# MovingHeadV2.net
KiCad netlist of a schematic drawn in EAGLE
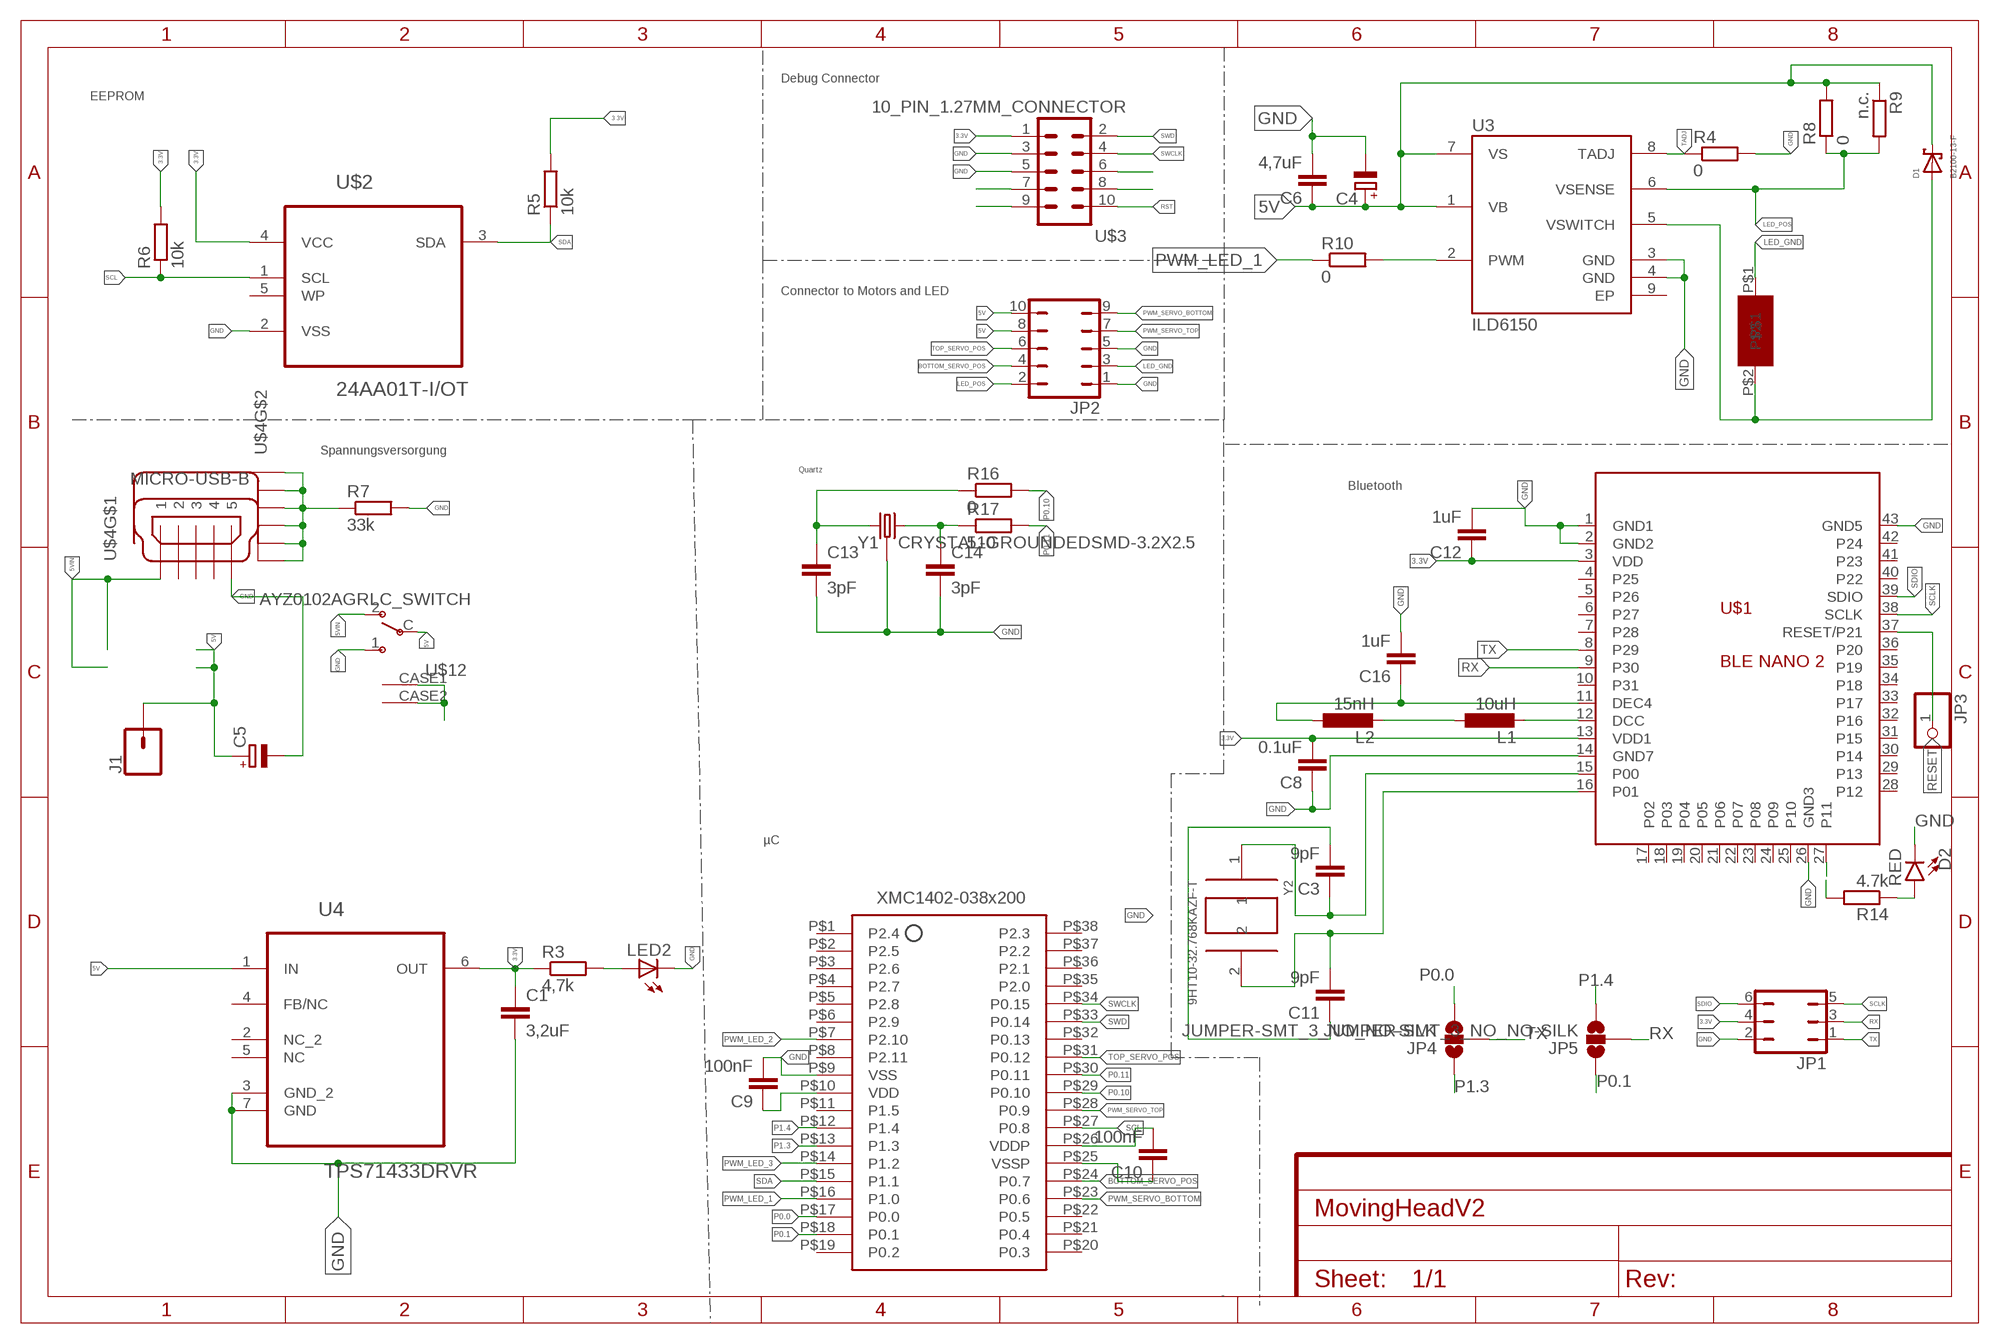
[diagram p0: schematic, sheet 1]

(export (version "E")
  (design (tool "Eeschema 10.0.6"))
  (components
    (comp (ref "C1")
      (value "3,2uF")
      (footprint "eagle-import:C0805")
      (libsource (lib "eagle-import") (part "rcl_334_C-EUC0805"))
    )
    (comp (ref "C3")
      (value "9pF")
      (footprint "eagle-import:C0805")
      (libsource (lib "eagle-import") (part "C-EUC0805"))
    )
    (comp (ref "C4")
      (value "CPOL-EUD")
      (footprint "eagle-import:PANASONIC_D")
      (libsource (lib "eagle-import") (part "CPOL-EUD"))
    )
    (comp (ref "C5")
      (value "CPOL-EUB/3528-21R")
      (footprint "eagle-import:B_3528-21R")
      (libsource (lib "eagle-import") (part "CPOL-EUB/3528-21R"))
    )
    (comp (ref "C6")
      (value "4,7uF")
      (footprint "eagle-import:C0805")
      (libsource (lib "eagle-import") (part "rcl_334_C-EUC0805"))
    )
    (comp (ref "C8")
      (value "0.1uF")
      (footprint "eagle-import:C0805")
      (libsource (lib "eagle-import") (part "C-EUC0805"))
    )
    (comp (ref "C9")
      (value "100nF")
      (footprint "eagle-import:C0805")
      (libsource (lib "eagle-import") (part "rcl_334_C-EUC0805"))
    )
    (comp (ref "C10")
      (value "100nF")
      (footprint "eagle-import:C0805")
      (libsource (lib "eagle-import") (part "rcl_334_C-EUC0805"))
    )
    (comp (ref "C11")
      (value "9pF")
      (footprint "eagle-import:C0805")
      (libsource (lib "eagle-import") (part "C-EUC0805"))
    )
    (comp (ref "C12")
      (value "1uF")
      (footprint "eagle-import:C0603")
      (libsource (lib "eagle-import") (part "C-EUC0603"))
    )
    (comp (ref "C13")
      (value "3pF")
      (footprint "eagle-import:C0805")
      (libsource (lib "eagle-import") (part "C-EUC0805"))
    )
    (comp (ref "C14")
      (value "3pF")
      (footprint "eagle-import:C0805")
      (libsource (lib "eagle-import") (part "C-EUC0805"))
    )
    (comp (ref "C16")
      (value "1uF")
      (footprint "eagle-import:C0603")
      (libsource (lib "eagle-import") (part "C-EUC0603"))
    )
    (comp (ref "D1")
      (value "B2100-13-F")
      (footprint "eagle-import:SMB")
      (fields
        (field (name "MANUFACTURER_1_PART_NUMBER") "B220-13-F")
        (field (name "MANUFACTURER_2_PART_NUMBER") "Diverse")
      )
      (libsource (lib "eagle-import") (part "B220"))
    )
    (comp (ref "D2")
      (value "RED")
      (footprint "eagle-import:LED-0603")
      (libsource (lib "eagle-import") (part "LED-RED0603"))
    )
    (comp (ref "J1")
      (value "CONN_01")
      (footprint "eagle-import:1X01")
      (libsource (lib "eagle-import") (part "CONN_01"))
    )
    (comp (ref "JP1")
      (value "JP3Q")
      (footprint "eagle-import:JP3Q")
      (libsource (lib "eagle-import") (part "JP3Q"))
    )
    (comp (ref "JP2")
      (value "JP5Q")
      (footprint "eagle-import:JP5Q")
      (libsource (lib "eagle-import") (part "JP5Q"))
    )
    (comp (ref "JP3")
      (value "PINHD-1X1")
      (footprint "eagle-import:1X01")
      (libsource (lib "eagle-import") (part "PINHD-1X1"))
    )
    (comp (ref "JP4")
      (value "JUMPER-SMT_3_NO_NO-SILK")
      (footprint "eagle-import:SMT-JUMPER_3_NO_NO-SILK")
      (libsource (lib "eagle-import") (part "JUMPER-SMT_3_NO_NO-SILK"))
    )
    (comp (ref "JP5")
      (value "JUMPER-SMT_3_NO_NO-SILK")
      (footprint "eagle-import:SMT-JUMPER_3_NO_NO-SILK")
      (libsource (lib "eagle-import") (part "JUMPER-SMT_3_NO_NO-SILK"))
    )
    (comp (ref "L1")
      (value "10uH")
      (footprint "eagle-import:L2012C")
      (libsource (lib "eagle-import") (part "L-EUL2012C"))
    )
    (comp (ref "L2")
      (value "15nH")
      (footprint "eagle-import:L2012C")
      (libsource (lib "eagle-import") (part "L-EUL2012C"))
    )
    (comp (ref "LED2")
      (value "LEDCHIPLED_0805")
      (footprint "eagle-import:CHIPLED_0805")
      (libsource (lib "eagle-import") (part "LEDCHIPLED_0805"))
    )
    (comp (ref "R3")
      (value "4,7k")
      (footprint "eagle-import:R0805")
      (libsource (lib "eagle-import") (part "rcl_334_R-EU_R0805"))
    )
    (comp (ref "R4")
      (value "0")
      (footprint "eagle-import:R0805")
      (libsource (lib "eagle-import") (part "rcl_334_R-EU_R0805"))
    )
    (comp (ref "R5")
      (value "10k")
      (footprint "eagle-import:R0805")
      (libsource (lib "eagle-import") (part "rcl_334_R-EU_R0805"))
    )
    (comp (ref "R6")
      (value "10k")
      (footprint "eagle-import:R0805")
      (libsource (lib "eagle-import") (part "rcl_334_R-EU_R0805"))
    )
    (comp (ref "R7")
      (value "33k")
      (footprint "eagle-import:R0805")
      (libsource (lib "eagle-import") (part "rcl_334_R-EU_R0805"))
    )
    (comp (ref "R8")
      (value "0")
      (footprint "eagle-import:R0805")
      (libsource (lib "eagle-import") (part "rcl_334_R-EU_R0805"))
    )
    (comp (ref "R9")
      (value "n.c.")
      (footprint "eagle-import:R0805")
      (libsource (lib "eagle-import") (part "rcl_334_R-EU_R0805"))
    )
    (comp (ref "R10")
      (value "0")
      (footprint "eagle-import:R0805")
      (libsource (lib "eagle-import") (part "rcl_334_R-EU_R0805"))
    )
    (comp (ref "R14")
      (value "4.7k")
      (footprint "eagle-import:R0805")
      (libsource (lib "eagle-import") (part "R-EU_R0805"))
    )
    (comp (ref "R16")
      (value "0")
      (footprint "eagle-import:R0805")
      (libsource (lib "eagle-import") (part "R-EU_R0805"))
    )
    (comp (ref "R17")
      (value "510")
      (footprint "eagle-import:R0805")
      (libsource (lib "eagle-import") (part "R-EU_R0805"))
    )
    (comp (ref "U$1")
      (value "BLE NANO 2")
      (footprint "eagle-import:RBT07")
      (libsource (lib "eagle-import") (part "RBT07"))
    )
    (comp (ref "U$2")
      (value "24AA01T-I/OT")
      (footprint "eagle-import:SOT95P270X145-5N")
      (libsource (lib "eagle-import") (part "24AA01T-I/OT"))
    )
    (comp (ref "U$3")
      (value "10_PIN_1.27MM_CONNECTOR")
      (footprint "eagle-import:10_PIN_1.27MM")
      (libsource (lib "eagle-import") (part "10_PIN_1.27MM_CONNECTOR"))
    )
    (comp (ref "U$4")
      (value "MICRO-USB-B")
      (footprint "eagle-import:MICRO_USB_B")
      (libsource (lib "eagle-import") (part "MICRO-USB-B"))
    )
    (comp (ref "U$7")
      (value "CUSTOMCOIL6.8UH")
      (footprint "eagle-import:CUSTOMCOIL6.8UH")
      (libsource (lib "eagle-import") (part "CUSTOMCOIL6.8UH"))
    )
    (comp (ref "U$10")
      (value "XMC1400_38P")
      (footprint "eagle-import:XMC1400_38P")
      (libsource (lib "eagle-import") (part "XMC1400_38P"))
    )
    (comp (ref "U$12")
      (value "AYZ0102AGRLC_SWITCH")
      (footprint "eagle-import:AYZ0102AGRLC")
      (libsource (lib "eagle-import") (part "AYZ0102AGRLC_SWITCH"))
    )
    (comp (ref "U3")
      (value "ILD6150")
      (footprint "eagle-import:SOIC127P600X170-9N-V2")
      (libsource (lib "eagle-import") (part "ILD6150"))
    )
    (comp (ref "U4")
      (value "TPS71433DRVR")
      (footprint "eagle-import:SON65P200X200X80-7N")
      (fields (field (name "MF") "Texas Instruments"))
      (libsource (lib "eagle-import") (part "TPS71433DRVR"))
    )
    (comp (ref "Y1")
      (value "CRYSTAL-GROUNDEDSMD-3.2X2.5")
      (footprint "eagle-import:CRYSTAL-SMD-3.2X2.5MM")
      (libsource (lib "eagle-import") (part "CRYSTAL-GROUNDEDSMD-3.2X2.5"))
    )
    (comp (ref "Y2")
      (value "9HT10-32.768KAZF-T")
      (footprint "eagle-import:XTAL320X150X75")
      (libsource (lib "eagle-import") (part "9HT10-32.768KAZF-T"))
    )
  )
  (nets
    (net (code "1") (name "/EP") (class "Default")
      (node (ref "U3") (pin "9") (pinfunction "EP_9") (pintype "power_in"))
    )
    (net (code "2") (name "3.3V") (class "Default")
      (node (ref "C1") (pin "1") (pinfunction "1_1") (pintype "passive"))
      (node (ref "C10") (pin "2") (pinfunction "2_2") (pintype "passive"))
      (node (ref "C12") (pin "1") (pinfunction "1_1") (pintype "passive"))
      (node (ref "C8") (pin "2") (pinfunction "2_2") (pintype "passive"))
      (node (ref "C9") (pin "1") (pinfunction "1_1") (pintype "passive"))
      (node (ref "JP1") (pin "4") (pinfunction "4_4") (pintype "passive"))
      (node (ref "R3") (pin "1") (pinfunction "1_1") (pintype "passive"))
      (node (ref "R5") (pin "2") (pinfunction "2_2") (pintype "passive"))
      (node (ref "R6") (pin "2") (pinfunction "2_2") (pintype "passive"))
      (node (ref "U$1") (pin "13") (pinfunction "VDD1_13") (pintype "bidirectional"))
      (node (ref "U$1") (pin "3") (pinfunction "VDD_3") (pintype "bidirectional"))
      (node (ref "U$10") (pin "P$10") (pinfunction "VDD_P$10") (pintype "bidirectional"))
      (node (ref "U$10") (pin "P$26") (pinfunction "VDDP_P$26") (pintype "bidirectional"))
      (node (ref "U$2") (pin "4") (pinfunction "VCC_4") (pintype "power_in"))
      (node (ref "U$3") (pin "1") (pinfunction "1_1") (pintype "passive"))
      (node (ref "U4") (pin "6") (pinfunction "OUT_6") (pintype "output"))
    )
    (net (code "3") (name "5V") (class "Default")
      (node (ref "C4") (pin "+") (pinfunction "+_+") (pintype "passive"))
      (node (ref "C5") (pin "+") (pinfunction "+_+") (pintype "passive"))
      (node (ref "C6") (pin "1") (pinfunction "1_1") (pintype "passive"))
      (node (ref "D1") (pin "C") (pinfunction "C_C") (pintype "passive"))
      (node (ref "J1") (pin "1") (pinfunction "1_1") (pintype "passive"))
      (node (ref "JP2") (pin "10") (pinfunction "10_10") (pintype "passive"))
      (node (ref "JP2") (pin "8") (pinfunction "8_8") (pintype "passive"))
      (node (ref "R8") (pin "2") (pinfunction "2_2") (pintype "passive"))
      (node (ref "R9") (pin "1") (pinfunction "1_1") (pintype "passive"))
      (node (ref "U$12") (pin "C") (pinfunction "C_C") (pintype "passive"))
      (node (ref "U3") (pin "1") (pinfunction "VB_1") (pintype "input"))
      (node (ref "U3") (pin "7") (pinfunction "VS_7") (pintype "power_in"))
      (node (ref "U4") (pin "1") (pinfunction "IN_1") (pintype "power_in"))
    )
    (net (code "4") (name "5VIN") (class "Default")
      (node (ref "U$12") (pin "2") (pinfunction "2_2") (pintype "passive"))
      (node (ref "U$4") (pin "1") (pinfunction "1_1") (pintype "passive"))
    )
    (net (code "5") (name "BOTTOM_SERVO_POS") (class "Default")
      (node (ref "JP2") (pin "4") (pinfunction "4_4") (pintype "passive"))
      (node (ref "U$10") (pin "P$24") (pinfunction "P0.7_P$24") (pintype "bidirectional"))
    )
    (net (code "6") (name "GND") (class "Default")
      (node (ref "C1") (pin "2") (pinfunction "2_2") (pintype "passive"))
      (node (ref "C10") (pin "1") (pinfunction "1_1") (pintype "passive"))
      (node (ref "C11") (pin "1") (pinfunction "1_1") (pintype "passive"))
      (node (ref "C12") (pin "2") (pinfunction "2_2") (pintype "passive"))
      (node (ref "C13") (pin "2") (pinfunction "2_2") (pintype "passive"))
      (node (ref "C14") (pin "2") (pinfunction "2_2") (pintype "passive"))
      (node (ref "C16") (pin "2") (pinfunction "2_2") (pintype "passive"))
      (node (ref "C3") (pin "2") (pinfunction "2_2") (pintype "passive"))
      (node (ref "C4") (pin "-") (pinfunction "-_-") (pintype "passive"))
      (node (ref "C5") (pin "-") (pinfunction "-_-") (pintype "passive"))
      (node (ref "C6") (pin "2") (pinfunction "2_2") (pintype "passive"))
      (node (ref "C8") (pin "1") (pinfunction "1_1") (pintype "passive"))
      (node (ref "C9") (pin "2") (pinfunction "2_2") (pintype "passive"))
      (node (ref "D2") (pin "C") (pinfunction "C_C") (pintype "passive"))
      (node (ref "JP1") (pin "2") (pinfunction "2_2") (pintype "passive"))
      (node (ref "JP2") (pin "1") (pinfunction "1_1") (pintype "passive"))
      (node (ref "JP2") (pin "5") (pinfunction "5_5") (pintype "passive"))
      (node (ref "LED2") (pin "C") (pinfunction "C_C") (pintype "passive"))
      (node (ref "R4") (pin "2") (pinfunction "2_2") (pintype "passive"))
      (node (ref "R7") (pin "2") (pinfunction "2_2") (pintype "passive"))
      (node (ref "U$1") (pin "1") (pinfunction "GND1_1") (pintype "bidirectional"))
      (node (ref "U$1") (pin "14") (pinfunction "GND7_14") (pintype "bidirectional"))
      (node (ref "U$1") (pin "2") (pinfunction "GND2_2") (pintype "bidirectional"))
      (node (ref "U$1") (pin "26") (pinfunction "GND3_26") (pintype "bidirectional"))
      (node (ref "U$1") (pin "43") (pinfunction "GND5_43") (pintype "bidirectional"))
      (node (ref "U$10") (pin "P$25") (pinfunction "VSSP_P$25") (pintype "bidirectional"))
      (node (ref "U$10") (pin "P$9") (pinfunction "VSS_P$9") (pintype "bidirectional"))
      (node (ref "U$12") (pin "1") (pinfunction "1_1") (pintype "passive"))
      (node (ref "U$12") (pin "CASE1") (pinfunction "CASE1_CASE1") (pintype "bidirectional"))
      (node (ref "U$12") (pin "CASE2") (pinfunction "CASE2_CASE2") (pintype "bidirectional"))
      (node (ref "U$2") (pin "2") (pinfunction "VSS_2") (pintype "passive"))
      (node (ref "U$3") (pin "3") (pinfunction "3_3") (pintype "passive"))
      (node (ref "U$3") (pin "5") (pinfunction "5_5") (pintype "passive"))
      (node (ref "U$4") (pin "5") (pinfunction "5_5") (pintype "passive"))
      (node (ref "U3") (pin "3") (pinfunction "GND_3") (pintype "power_in"))
      (node (ref "U3") (pin "4") (pinfunction "GND_4") (pintype "power_in"))
      (node (ref "U4") (pin "3") (pinfunction "GND_2_3") (pintype "passive"))
      (node (ref "U4") (pin "7") (pinfunction "GND_7") (pintype "passive"))
      (node (ref "Y1") (pin "2") (pinfunction "3_2") (pintype "passive"))
      (node (ref "Y1") (pin "4") (pinfunction "3_4") (pintype "passive"))
    )
    (net (code "7") (name "LED_GND") (class "Default")
      (node (ref "JP2") (pin "3") (pinfunction "3_3") (pintype "passive"))
      (node (ref "U$7") (pin "P$1") (pinfunction "P$1_P$1") (pintype "bidirectional"))
    )
    (net (code "8") (name "LED_POS") (class "Default")
      (node (ref "JP2") (pin "2") (pinfunction "2_2") (pintype "passive"))
      (node (ref "R8") (pin "1") (pinfunction "1_1") (pintype "passive"))
      (node (ref "R9") (pin "2") (pinfunction "2_2") (pintype "passive"))
      (node (ref "U3") (pin "6") (pinfunction "VSENSE_6") (pintype "input"))
    )
    (net (code "9") (name "Net-(C13-Pad1)") (class "Default")
      (node (ref "C13") (pin "1") (pinfunction "1_1") (pintype "passive"))
      (node (ref "R16") (pin "1") (pinfunction "1_1") (pintype "passive"))
      (node (ref "Y1") (pin "1") (pinfunction "1_1") (pintype "passive"))
    )
    (net (code "10") (name "Net-(D2-PadA)") (class "Default")
      (node (ref "D2") (pin "A") (pinfunction "A_A") (pintype "passive"))
      (node (ref "R14") (pin "1") (pinfunction "1_1") (pintype "passive"))
    )
    (net (code "11") (name "Net-(L1-Pad1)") (class "Default")
      (node (ref "L1") (pin "1") (pinfunction "1_1") (pintype "passive"))
      (node (ref "L2") (pin "2") (pinfunction "2_2") (pintype "passive"))
    )
    (net (code "12") (name "Net-(LED2-PadA)") (class "Default")
      (node (ref "LED2") (pin "A") (pinfunction "A_A") (pintype "passive"))
      (node (ref "R3") (pin "2") (pinfunction "2_2") (pintype "passive"))
    )
    (net (code "13") (name "Net-(U$1-DCC)") (class "Default")
      (node (ref "L1") (pin "2") (pinfunction "2_2") (pintype "passive"))
      (node (ref "U$1") (pin "12") (pinfunction "DCC_12") (pintype "bidirectional"))
    )
    (net (code "14") (name "Net-(U$1-DEC4)") (class "Default")
      (node (ref "C16") (pin "1") (pinfunction "1_1") (pintype "passive"))
      (node (ref "L2") (pin "1") (pinfunction "1_1") (pintype "passive"))
      (node (ref "U$1") (pin "11") (pinfunction "DEC4_11") (pintype "bidirectional"))
    )
    (net (code "15") (name "Net-(U$1-P00)") (class "Default")
      (node (ref "C3") (pin "1") (pinfunction "1_1") (pintype "passive"))
      (node (ref "U$1") (pin "15") (pinfunction "P00_15") (pintype "bidirectional"))
      (node (ref "Y2") (pin "1") (pinfunction "1_1") (pintype "passive"))
    )
    (net (code "16") (name "Net-(U$1-P01)") (class "Default")
      (node (ref "C11") (pin "2") (pinfunction "2_2") (pintype "passive"))
      (node (ref "U$1") (pin "16") (pinfunction "P01_16") (pintype "bidirectional"))
      (node (ref "Y2") (pin "2") (pinfunction "2_2") (pintype "passive"))
    )
    (net (code "17") (name "Net-(U$1-P11)") (class "Default")
      (node (ref "R14") (pin "2") (pinfunction "2_2") (pintype "passive"))
      (node (ref "U$1") (pin "27") (pinfunction "P11_27") (pintype "bidirectional"))
    )
    (net (code "18") (name "Net-(U$4B-S1)") (class "Default")
      (node (ref "R7") (pin "1") (pinfunction "1_1") (pintype "passive"))
      (node (ref "U$4") (pin "P$1") (pinfunction "S1_P$1") (pintype "passive"))
      (node (ref "U$4") (pin "P$10") (pinfunction "S6_P$10") (pintype "passive"))
      (node (ref "U$4") (pin "P$2") (pinfunction "S2_P$2") (pintype "passive"))
      (node (ref "U$4") (pin "P$6") (pinfunction "S3_P$6") (pintype "passive"))
      (node (ref "U$4") (pin "P$7") (pinfunction "S4_P$7") (pintype "passive"))
      (node (ref "U$4") (pin "P$9") (pinfunction "S5_P$9") (pintype "passive"))
    )
    (net (code "19") (name "Net-(U3-PWM)") (class "Default")
      (node (ref "R10") (pin "2") (pinfunction "2_2") (pintype "passive"))
      (node (ref "U3") (pin "2") (pinfunction "PWM_2") (pintype "input"))
    )
    (net (code "20") (name "Net-(U3-VSWITCH)") (class "Default")
      (node (ref "D1") (pin "A") (pinfunction "A_A") (pintype "passive"))
      (node (ref "U$7") (pin "P$2") (pinfunction "P$2_P$2") (pintype "bidirectional"))
      (node (ref "U3") (pin "5") (pinfunction "VSWITCH_5") (pintype "output"))
    )
    (net (code "21") (name "Net-(Y1-2)") (class "Default")
      (node (ref "C14") (pin "1") (pinfunction "1_1") (pintype "passive"))
      (node (ref "R17") (pin "1") (pinfunction "1_1") (pintype "passive"))
      (node (ref "Y1") (pin "3") (pinfunction "2_3") (pintype "passive"))
    )
    (net (code "22") (name "P0.0") (class "Default")
      (node (ref "JP4") (pin "3") (pinfunction "3_3") (pintype "passive"))
      (node (ref "U$10") (pin "P$17") (pinfunction "P0.0_P$17") (pintype "bidirectional"))
    )
    (net (code "23") (name "P0.1") (class "Default")
      (node (ref "JP5") (pin "1") (pinfunction "1_1") (pintype "passive"))
      (node (ref "U$10") (pin "P$18") (pinfunction "P0.1_P$18") (pintype "bidirectional"))
    )
    (net (code "24") (name "P0.10") (class "Default")
      (node (ref "R16") (pin "2") (pinfunction "2_2") (pintype "passive"))
      (node (ref "U$10") (pin "P$29") (pinfunction "P0.10_P$29") (pintype "bidirectional"))
    )
    (net (code "25") (name "P0.11") (class "Default")
      (node (ref "R17") (pin "2") (pinfunction "2_2") (pintype "passive"))
      (node (ref "U$10") (pin "P$30") (pinfunction "P0.11_P$30") (pintype "bidirectional"))
    )
    (net (code "26") (name "P1.3") (class "Default")
      (node (ref "JP4") (pin "1") (pinfunction "1_1") (pintype "passive"))
      (node (ref "U$10") (pin "P$13") (pinfunction "P1.3_P$13") (pintype "bidirectional"))
    )
    (net (code "27") (name "P1.4") (class "Default")
      (node (ref "JP5") (pin "3") (pinfunction "3_3") (pintype "passive"))
      (node (ref "U$10") (pin "P$12") (pinfunction "P1.4_P$12") (pintype "bidirectional"))
    )
    (net (code "28") (name "PWM_LED_1") (class "Default")
      (node (ref "R10") (pin "1") (pinfunction "1_1") (pintype "passive"))
      (node (ref "U$10") (pin "P$16") (pinfunction "P1.0_P$16") (pintype "bidirectional"))
    )
    (net (code "29") (name "PWM_LED_2") (class "Default")
      (node (ref "U$10") (pin "P$7") (pinfunction "P2.10_P$7") (pintype "bidirectional"))
    )
    (net (code "30") (name "PWM_LED_3") (class "Default")
      (node (ref "U$10") (pin "P$14") (pinfunction "P1.2_P$14") (pintype "bidirectional"))
    )
    (net (code "31") (name "PWM_SERVO_BOTTOM") (class "Default")
      (node (ref "JP2") (pin "9") (pinfunction "9_9") (pintype "passive"))
      (node (ref "U$10") (pin "P$23") (pinfunction "P0.6_P$23") (pintype "bidirectional"))
    )
    (net (code "32") (name "PWM_SERVO_TOP") (class "Default")
      (node (ref "JP2") (pin "7") (pinfunction "7_7") (pintype "passive"))
      (node (ref "U$10") (pin "P$28") (pinfunction "P0.9_P$28") (pintype "bidirectional"))
    )
    (net (code "33") (name "RESET") (class "Default")
      (node (ref "JP3") (pin "1") (pinfunction "1_1") (pintype "passive"))
      (node (ref "U$1") (pin "37") (pinfunction "RESET/P21_37") (pintype "bidirectional"))
    )
    (net (code "34") (name "RST") (class "Default")
      (node (ref "U$3") (pin "10") (pinfunction "10_10") (pintype "passive"))
    )
    (net (code "35") (name "RX") (class "Default")
      (node (ref "JP1") (pin "3") (pinfunction "3_3") (pintype "passive"))
      (node (ref "JP5") (pin "2") (pinfunction "2_2") (pintype "passive"))
      (node (ref "U$1") (pin "9") (pinfunction "P30_9") (pintype "bidirectional"))
    )
    (net (code "36") (name "SCL") (class "Default")
      (node (ref "R6") (pin "1") (pinfunction "1_1") (pintype "passive"))
      (node (ref "U$10") (pin "P$27") (pinfunction "P0.8_P$27") (pintype "bidirectional"))
      (node (ref "U$2") (pin "1") (pinfunction "SCL_1") (pintype "input"))
    )
    (net (code "37") (name "SCLK") (class "Default")
      (node (ref "JP1") (pin "5") (pinfunction "5_5") (pintype "passive"))
      (node (ref "U$1") (pin "38") (pinfunction "SCLK_38") (pintype "bidirectional"))
    )
    (net (code "38") (name "SDA") (class "Default")
      (node (ref "R5") (pin "1") (pinfunction "1_1") (pintype "passive"))
      (node (ref "U$10") (pin "P$15") (pinfunction "P1.1_P$15") (pintype "bidirectional"))
      (node (ref "U$2") (pin "3") (pinfunction "SDA_3") (pintype "bidirectional"))
    )
    (net (code "39") (name "SDIO") (class "Default")
      (node (ref "JP1") (pin "6") (pinfunction "6_6") (pintype "passive"))
      (node (ref "U$1") (pin "39") (pinfunction "SDIO_39") (pintype "bidirectional"))
    )
    (net (code "40") (name "SWCLK") (class "Default")
      (node (ref "U$10") (pin "P$34") (pinfunction "P0.15_P$34") (pintype "bidirectional"))
      (node (ref "U$3") (pin "4") (pinfunction "4_4") (pintype "passive"))
    )
    (net (code "41") (name "SWD") (class "Default")
      (node (ref "U$10") (pin "P$33") (pinfunction "P0.14_P$33") (pintype "bidirectional"))
      (node (ref "U$3") (pin "2") (pinfunction "2_2") (pintype "passive"))
    )
    (net (code "42") (name "TADJ") (class "Default")
      (node (ref "R4") (pin "1") (pinfunction "1_1") (pintype "passive"))
      (node (ref "U3") (pin "8") (pinfunction "TADJ_8") (pintype "output"))
    )
    (net (code "43") (name "TOP_SERVO_POS") (class "Default")
      (node (ref "JP2") (pin "6") (pinfunction "6_6") (pintype "passive"))
      (node (ref "U$10") (pin "P$31") (pinfunction "P0.12_P$31") (pintype "bidirectional"))
    )
    (net (code "44") (name "TX") (class "Default")
      (node (ref "JP1") (pin "1") (pinfunction "1_1") (pintype "passive"))
      (node (ref "JP4") (pin "2") (pinfunction "2_2") (pintype "passive"))
      (node (ref "U$1") (pin "8") (pinfunction "P29_8") (pintype "bidirectional"))
    )
    (net (code "45") (name "unconnected-(U$1-P02-Pad17)") (class "Default")
      (node (ref "U$1") (pin "17") (pinfunction "P02_17") (pintype "bidirectional"))
    )
    (net (code "46") (name "unconnected-(U$1-P03-Pad18)") (class "Default")
      (node (ref "U$1") (pin "18") (pinfunction "P03_18") (pintype "bidirectional"))
    )
    (net (code "47") (name "unconnected-(U$1-P04-Pad19)") (class "Default")
      (node (ref "U$1") (pin "19") (pinfunction "P04_19") (pintype "bidirectional"))
    )
    (net (code "48") (name "unconnected-(U$1-P05-Pad20)") (class "Default")
      (node (ref "U$1") (pin "20") (pinfunction "P05_20") (pintype "bidirectional"))
    )
    (net (code "49") (name "unconnected-(U$1-P06-Pad21)") (class "Default")
      (node (ref "U$1") (pin "21") (pinfunction "P06_21") (pintype "bidirectional"))
    )
    (net (code "50") (name "unconnected-(U$1-P07-Pad22)") (class "Default")
      (node (ref "U$1") (pin "22") (pinfunction "P07_22") (pintype "bidirectional"))
    )
    (net (code "51") (name "unconnected-(U$1-P08-Pad23)") (class "Default")
      (node (ref "U$1") (pin "23") (pinfunction "P08_23") (pintype "bidirectional"))
    )
    (net (code "52") (name "unconnected-(U$1-P09-Pad24)") (class "Default")
      (node (ref "U$1") (pin "24") (pinfunction "P09_24") (pintype "bidirectional"))
    )
    (net (code "53") (name "unconnected-(U$1-P10-Pad25)") (class "Default")
      (node (ref "U$1") (pin "25") (pinfunction "P10_25") (pintype "bidirectional"))
    )
    (net (code "54") (name "unconnected-(U$1-P12-Pad28)") (class "Default")
      (node (ref "U$1") (pin "28") (pinfunction "P12_28") (pintype "bidirectional"))
    )
    (net (code "55") (name "unconnected-(U$1-P13-Pad29)") (class "Default")
      (node (ref "U$1") (pin "29") (pinfunction "P13_29") (pintype "bidirectional"))
    )
    (net (code "56") (name "unconnected-(U$1-P14-Pad30)") (class "Default")
      (node (ref "U$1") (pin "30") (pinfunction "P14_30") (pintype "bidirectional"))
    )
    (net (code "57") (name "unconnected-(U$1-P15-Pad31)") (class "Default")
      (node (ref "U$1") (pin "31") (pinfunction "P15_31") (pintype "bidirectional"))
    )
    (net (code "58") (name "unconnected-(U$1-P16-Pad32)") (class "Default")
      (node (ref "U$1") (pin "32") (pinfunction "P16_32") (pintype "bidirectional"))
    )
    (net (code "59") (name "unconnected-(U$1-P17-Pad33)") (class "Default")
      (node (ref "U$1") (pin "33") (pinfunction "P17_33") (pintype "bidirectional"))
    )
    (net (code "60") (name "unconnected-(U$1-P18-Pad34)") (class "Default")
      (node (ref "U$1") (pin "34") (pinfunction "P18_34") (pintype "bidirectional"))
    )
    (net (code "61") (name "unconnected-(U$1-P19-Pad35)") (class "Default")
      (node (ref "U$1") (pin "35") (pinfunction "P19_35") (pintype "bidirectional"))
    )
    (net (code "62") (name "unconnected-(U$1-P20-Pad36)") (class "Default")
      (node (ref "U$1") (pin "36") (pinfunction "P20_36") (pintype "bidirectional"))
    )
    (net (code "63") (name "unconnected-(U$1-P22-Pad40)") (class "Default")
      (node (ref "U$1") (pin "40") (pinfunction "P22_40") (pintype "bidirectional"))
    )
    (net (code "64") (name "unconnected-(U$1-P23-Pad41)") (class "Default")
      (node (ref "U$1") (pin "41") (pinfunction "P23_41") (pintype "bidirectional"))
    )
    (net (code "65") (name "unconnected-(U$1-P24-Pad42)") (class "Default")
      (node (ref "U$1") (pin "42") (pinfunction "P24_42") (pintype "bidirectional"))
    )
    (net (code "66") (name "unconnected-(U$1-P25-Pad4)") (class "Default")
      (node (ref "U$1") (pin "4") (pinfunction "P25_4") (pintype "bidirectional"))
    )
    (net (code "67") (name "unconnected-(U$1-P26-Pad5)") (class "Default")
      (node (ref "U$1") (pin "5") (pinfunction "P26_5") (pintype "bidirectional"))
    )
    (net (code "68") (name "unconnected-(U$1-P27-Pad6)") (class "Default")
      (node (ref "U$1") (pin "6") (pinfunction "P27_6") (pintype "bidirectional"))
    )
    (net (code "69") (name "unconnected-(U$1-P28-Pad7)") (class "Default")
      (node (ref "U$1") (pin "7") (pinfunction "P28_7") (pintype "bidirectional"))
    )
    (net (code "70") (name "unconnected-(U$1-P31-Pad10)") (class "Default")
      (node (ref "U$1") (pin "10") (pinfunction "P31_10") (pintype "bidirectional"))
    )
    (net (code "71") (name "unconnected-(U$2-WP-Pad5)") (class "Default")
      (node (ref "U$2") (pin "5") (pinfunction "WP_5") (pintype "input"))
    )
    (net (code "72") (name "unconnected-(U$3-Pad6)") (class "Default")
      (node (ref "U$3") (pin "6") (pinfunction "6_6") (pintype "passive"))
    )
    (net (code "73") (name "unconnected-(U$3-Pad7)") (class "Default")
      (node (ref "U$3") (pin "7") (pinfunction "7_7") (pintype "passive"))
    )
    (net (code "74") (name "unconnected-(U$3-Pad8)") (class "Default")
      (node (ref "U$3") (pin "8") (pinfunction "8_8") (pintype "passive"))
    )
    (net (code "75") (name "unconnected-(U$3-Pad9)") (class "Default")
      (node (ref "U$3") (pin "9") (pinfunction "9_9") (pintype "passive"))
    )
    (net (code "76") (name "unconnected-(U$4-Pad2)") (class "Default")
      (node (ref "U$4") (pin "2") (pinfunction "2_2") (pintype "passive"))
    )
    (net (code "77") (name "unconnected-(U$4-Pad3)") (class "Default")
      (node (ref "U$4") (pin "3") (pinfunction "3_3") (pintype "passive"))
    )
    (net (code "78") (name "unconnected-(U$4-Pad4)") (class "Default")
      (node (ref "U$4") (pin "4") (pinfunction "4_4") (pintype "passive"))
    )
    (net (code "79") (name "unconnected-(U$10-P0.2-PadP$19)") (class "Default")
      (node (ref "U$10") (pin "P$19") (pinfunction "P0.2_P$19") (pintype "bidirectional"))
    )
    (net (code "80") (name "unconnected-(U$10-P0.3-PadP$20)") (class "Default")
      (node (ref "U$10") (pin "P$20") (pinfunction "P0.3_P$20") (pintype "bidirectional"))
    )
    (net (code "81") (name "unconnected-(U$10-P0.4-PadP$21)") (class "Default")
      (node (ref "U$10") (pin "P$21") (pinfunction "P0.4_P$21") (pintype "bidirectional"))
    )
    (net (code "82") (name "unconnected-(U$10-P0.5-PadP$22)") (class "Default")
      (node (ref "U$10") (pin "P$22") (pinfunction "P0.5_P$22") (pintype "bidirectional"))
    )
    (net (code "83") (name "unconnected-(U$10-P0.13-PadP$32)") (class "Default")
      (node (ref "U$10") (pin "P$32") (pinfunction "P0.13_P$32") (pintype "bidirectional"))
    )
    (net (code "84") (name "unconnected-(U$10-P1.5-PadP$11)") (class "Default")
      (node (ref "U$10") (pin "P$11") (pinfunction "P1.5_P$11") (pintype "bidirectional"))
    )
    (net (code "85") (name "unconnected-(U$10-P2.0-PadP$35)") (class "Default")
      (node (ref "U$10") (pin "P$35") (pinfunction "P2.0_P$35") (pintype "bidirectional"))
    )
    (net (code "86") (name "unconnected-(U$10-P2.1-PadP$36)") (class "Default")
      (node (ref "U$10") (pin "P$36") (pinfunction "P2.1_P$36") (pintype "bidirectional"))
    )
    (net (code "87") (name "unconnected-(U$10-P2.2-PadP$37)") (class "Default")
      (node (ref "U$10") (pin "P$37") (pinfunction "P2.2_P$37") (pintype "bidirectional"))
    )
    (net (code "88") (name "unconnected-(U$10-P2.3-PadP$38)") (class "Default")
      (node (ref "U$10") (pin "P$38") (pinfunction "P2.3_P$38") (pintype "bidirectional"))
    )
    (net (code "89") (name "unconnected-(U$10-P2.4-PadP$1)") (class "Default")
      (node (ref "U$10") (pin "P$1") (pinfunction "P2.4_P$1") (pintype "bidirectional"))
    )
    (net (code "90") (name "unconnected-(U$10-P2.5-PadP$2)") (class "Default")
      (node (ref "U$10") (pin "P$2") (pinfunction "P2.5_P$2") (pintype "bidirectional"))
    )
    (net (code "91") (name "unconnected-(U$10-P2.6-PadP$3)") (class "Default")
      (node (ref "U$10") (pin "P$3") (pinfunction "P2.6_P$3") (pintype "bidirectional"))
    )
    (net (code "92") (name "unconnected-(U$10-P2.7-PadP$4)") (class "Default")
      (node (ref "U$10") (pin "P$4") (pinfunction "P2.7_P$4") (pintype "bidirectional"))
    )
    (net (code "93") (name "unconnected-(U$10-P2.8-PadP$5)") (class "Default")
      (node (ref "U$10") (pin "P$5") (pinfunction "P2.8_P$5") (pintype "bidirectional"))
    )
    (net (code "94") (name "unconnected-(U$10-P2.9-PadP$6)") (class "Default")
      (node (ref "U$10") (pin "P$6") (pinfunction "P2.9_P$6") (pintype "bidirectional"))
    )
    (net (code "95") (name "unconnected-(U$10-P2.11-PadP$8)") (class "Default")
      (node (ref "U$10") (pin "P$8") (pinfunction "P2.11_P$8") (pintype "bidirectional"))
    )
    (net (code "96") (name "unconnected-(U4-FB{slash}NC-Pad4)") (class "Default")
      (node (ref "U4") (pin "4") (pinfunction "FB/NC_4") (pintype "input"))
    )
    (net (code "97") (name "unconnected-(U4-NC-Pad5)") (class "Default")
      (node (ref "U4") (pin "5") (pinfunction "NC_5") (pintype "no_connect"))
    )
    (net (code "98") (name "unconnected-(U4-NC_2-Pad2)") (class "Default")
      (node (ref "U4") (pin "2") (pinfunction "NC_2_2") (pintype "no_connect"))
    )
  )
)
